# Caricabatteria_1_0.net
KiCad netlist of a schematic drawn in EAGLE
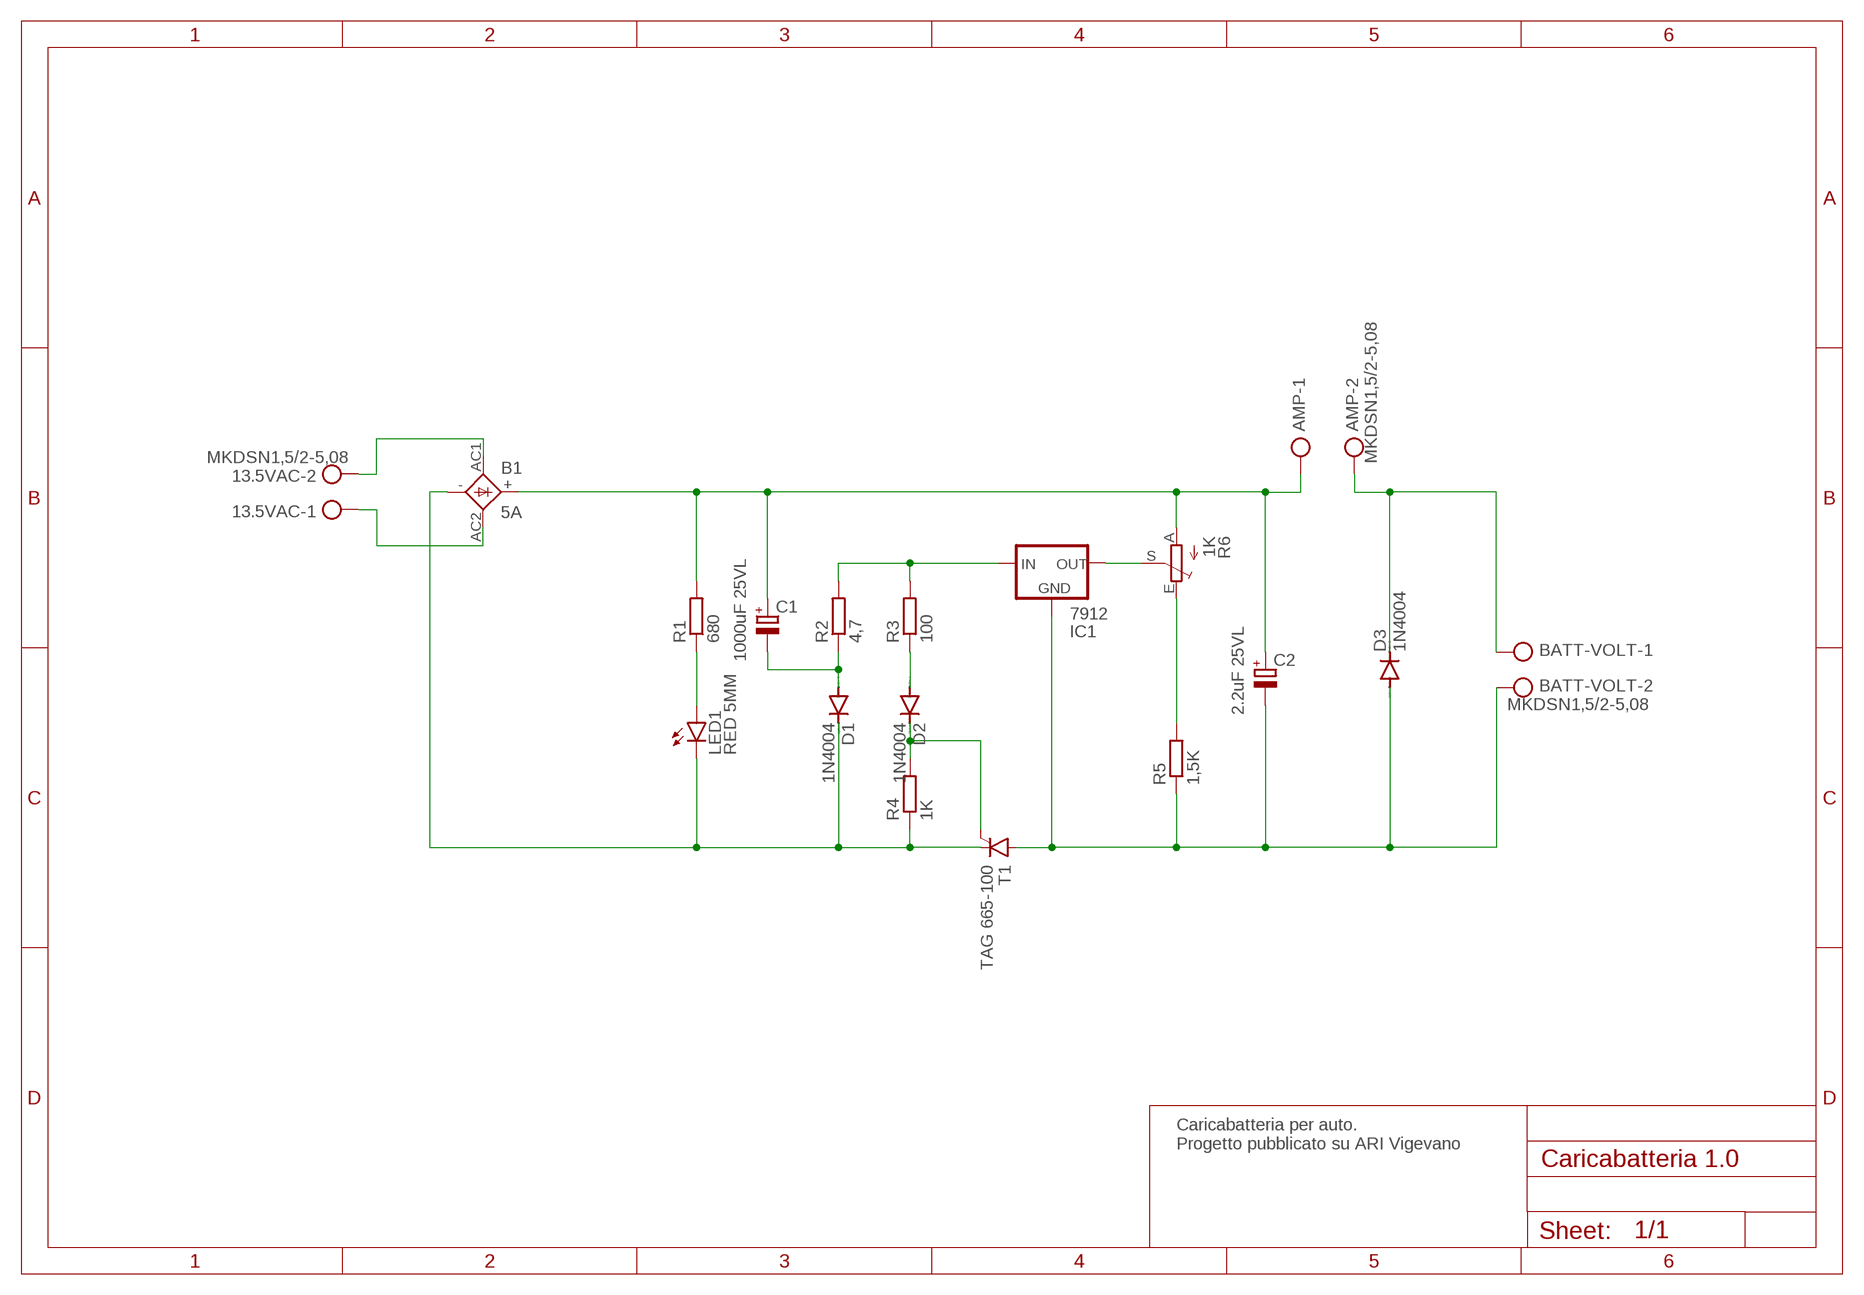
[diagram p0: schematic, sheet 1]

(export (version "E")
  (design (tool "Eeschema 10.0.6"))
  (components
    (comp (ref "13.5VAC")
      (value "MKDSN1,5/2-5,08")
      (footprint "eagle-import:MKDSN1,5_2-5,08")
      (libsource (lib "eagle-import") (part "MKDSN1,5/2-5,08"))
    )
    (comp (ref "AMP")
      (value "MKDSN1,5/2-5,08")
      (footprint "eagle-import:MKDSN1,5_2-5,08")
      (libsource (lib "eagle-import") (part "MKDSN1,5/2-5,08"))
    )
    (comp (ref "B1")
      (value "5A")
      (footprint "eagle-import:SKB")
      (libsource (lib "eagle-import") (part "SKB"))
    )
    (comp (ref "BATT-VOLT")
      (value "MKDSN1,5/2-5,08")
      (footprint "eagle-import:MKDSN1,5_2-5,08")
      (libsource (lib "eagle-import") (part "MKDSN1,5/2-5,08"))
    )
    (comp (ref "C1")
      (value "1000uF 25VL")
      (footprint "eagle-import:E5-10,5")
      (libsource (lib "eagle-import") (part "CPOL-EUE5-10.5"))
    )
    (comp (ref "C2")
      (value "2.2uF 25VL")
      (footprint "eagle-import:E5-10,5")
      (libsource (lib "eagle-import") (part "CPOL-EUE5-10.5"))
    )
    (comp (ref "D1")
      (value "1N4004")
      (footprint "eagle-import:DO41-10")
      (libsource (lib "eagle-import") (part "1N4004"))
    )
    (comp (ref "D2")
      (value "1N4004")
      (footprint "eagle-import:DO41-10")
      (libsource (lib "eagle-import") (part "1N4004"))
    )
    (comp (ref "D3")
      (value "1N4004")
      (footprint "eagle-import:DO41-10")
      (libsource (lib "eagle-import") (part "1N4004"))
    )
    (comp (ref "IC1")
      (value "7912")
      (footprint "eagle-import:79XXS")
      (libsource (lib "eagle-import") (part "79XXS"))
    )
    (comp (ref "LED1")
      (value "RED 5MM")
      (footprint "eagle-import:LED5MM")
      (libsource (lib "eagle-import") (part "LED5MM"))
    )
    (comp (ref "R1")
      (value "680")
      (footprint "eagle-import:0207_10")
      (libsource (lib "eagle-import") (part "R-EU_0207/10"))
    )
    (comp (ref "R2")
      (value "4,7")
      (footprint "eagle-import:0207_10")
      (libsource (lib "eagle-import") (part "R-EU_0207/10"))
    )
    (comp (ref "R3")
      (value "100")
      (footprint "eagle-import:0207_10")
      (libsource (lib "eagle-import") (part "R-EU_0207/10"))
    )
    (comp (ref "R4")
      (value "1K")
      (footprint "eagle-import:0207_10")
      (libsource (lib "eagle-import") (part "R-EU_0207/10"))
    )
    (comp (ref "R5")
      (value "1,5K")
      (footprint "eagle-import:0207_10")
      (libsource (lib "eagle-import") (part "R-EU_0207/10"))
    )
    (comp (ref "R6")
      (value "1K")
      (footprint "eagle-import:PT-10S")
      (libsource (lib "eagle-import") (part "TRIM_EU-PT10S"))
    )
    (comp (ref "T1")
      (value "TAG 665-100")
      (footprint "eagle-import:TOP3S-2")
      (libsource (lib "eagle-import") (part "BTW68"))
    )
  )
  (nets
    (net (code "1") (name "Net-(13.5VACA-KL)") (class "Default")
      (node (ref "13.5VAC") (pin "1") (pinfunction "KL_1") (pintype "passive"))
      (node (ref "B1") (pin "AC2") (pinfunction "AC2_AC2") (pintype "passive"))
    )
    (net (code "2") (name "Net-(13.5VACB-KL)") (class "Default")
      (node (ref "13.5VAC") (pin "2") (pinfunction "KL_2") (pintype "passive"))
      (node (ref "B1") (pin "AC1") (pinfunction "AC1_AC1") (pintype "passive"))
    )
    (net (code "3") (name "Net-(AMPA-KL)") (class "Default")
      (node (ref "AMP") (pin "1") (pinfunction "KL_1") (pintype "passive"))
      (node (ref "B1") (pin "+") (pinfunction "+_+") (pintype "passive"))
      (node (ref "C1") (pin "+") (pinfunction "+_+") (pintype "passive"))
      (node (ref "C2") (pin "+") (pinfunction "+_+") (pintype "passive"))
      (node (ref "R1") (pin "2") (pinfunction "2_2") (pintype "passive"))
      (node (ref "R6") (pin "A") (pinfunction "A_A") (pintype "passive"))
    )
    (net (code "4") (name "Net-(AMPB-KL)") (class "Default")
      (node (ref "AMP") (pin "2") (pinfunction "KL_2") (pintype "passive"))
      (node (ref "BATT-VOLT") (pin "1") (pinfunction "KL_1") (pintype "passive"))
      (node (ref "D3") (pin "C") (pinfunction "C_C") (pintype "passive"))
    )
    (net (code "5") (name "Net-(BATT-VOLTB-KL)") (class "Default")
      (node (ref "BATT-VOLT") (pin "2") (pinfunction "KL_2") (pintype "passive"))
      (node (ref "C2") (pin "-") (pinfunction "-_-") (pintype "passive"))
      (node (ref "D3") (pin "A") (pinfunction "A_A") (pintype "passive"))
      (node (ref "IC1") (pin "GND") (pinfunction "GND_GND") (pintype "input"))
      (node (ref "R5") (pin "1") (pinfunction "1_1") (pintype "passive"))
      (node (ref "T1") (pin "A") (pinfunction "A_A") (pintype "passive"))
    )
    (net (code "6") (name "Net-(C1-Pad-)") (class "Default")
      (node (ref "C1") (pin "-") (pinfunction "-_-") (pintype "passive"))
      (node (ref "D1") (pin "A") (pinfunction "A_A") (pintype "passive"))
      (node (ref "R2") (pin "1") (pinfunction "1_1") (pintype "passive"))
    )
    (net (code "7") (name "Net-(D2-PadA)") (class "Default")
      (node (ref "D2") (pin "A") (pinfunction "A_A") (pintype "passive"))
      (node (ref "R3") (pin "1") (pinfunction "1_1") (pintype "passive"))
    )
    (net (code "8") (name "Net-(D2-PadC)") (class "Default")
      (node (ref "D2") (pin "C") (pinfunction "C_C") (pintype "passive"))
      (node (ref "R4") (pin "2") (pinfunction "2_2") (pintype "passive"))
      (node (ref "T1") (pin "G") (pinfunction "G_G") (pintype "passive"))
    )
    (net (code "9") (name "Net-(IC1-PadIN)") (class "Default")
      (node (ref "IC1") (pin "IN") (pinfunction "IN_IN") (pintype "input"))
      (node (ref "R2") (pin "2") (pinfunction "2_2") (pintype "passive"))
      (node (ref "R3") (pin "2") (pinfunction "2_2") (pintype "passive"))
    )
    (net (code "10") (name "Net-(IC1-PadOUT)") (class "Default")
      (node (ref "IC1") (pin "OUT") (pinfunction "OUT_OUT") (pintype "passive"))
      (node (ref "R6") (pin "S") (pinfunction "S_S") (pintype "passive"))
    )
    (net (code "11") (name "Net-(LED1-C)") (class "Default")
      (node (ref "B1") (pin "-") (pinfunction "-_-") (pintype "passive"))
      (node (ref "D1") (pin "C") (pinfunction "C_C") (pintype "passive"))
      (node (ref "LED1") (pin "K") (pinfunction "C_K") (pintype "passive"))
      (node (ref "R4") (pin "1") (pinfunction "1_1") (pintype "passive"))
      (node (ref "T1") (pin "C") (pinfunction "C_C") (pintype "passive"))
    )
    (net (code "12") (name "Net-(LED1-PadA)") (class "Default")
      (node (ref "LED1") (pin "A") (pinfunction "A_A") (pintype "passive"))
      (node (ref "R1") (pin "1") (pinfunction "1_1") (pintype "passive"))
    )
    (net (code "13") (name "Net-(R5-Pad2)") (class "Default")
      (node (ref "R5") (pin "2") (pinfunction "2_2") (pintype "passive"))
      (node (ref "R6") (pin "E") (pinfunction "E_E") (pintype "passive"))
    )
  )
)
